# Eurorack_CV_Input.net
KiCad netlist of a schematic drawn in EAGLE
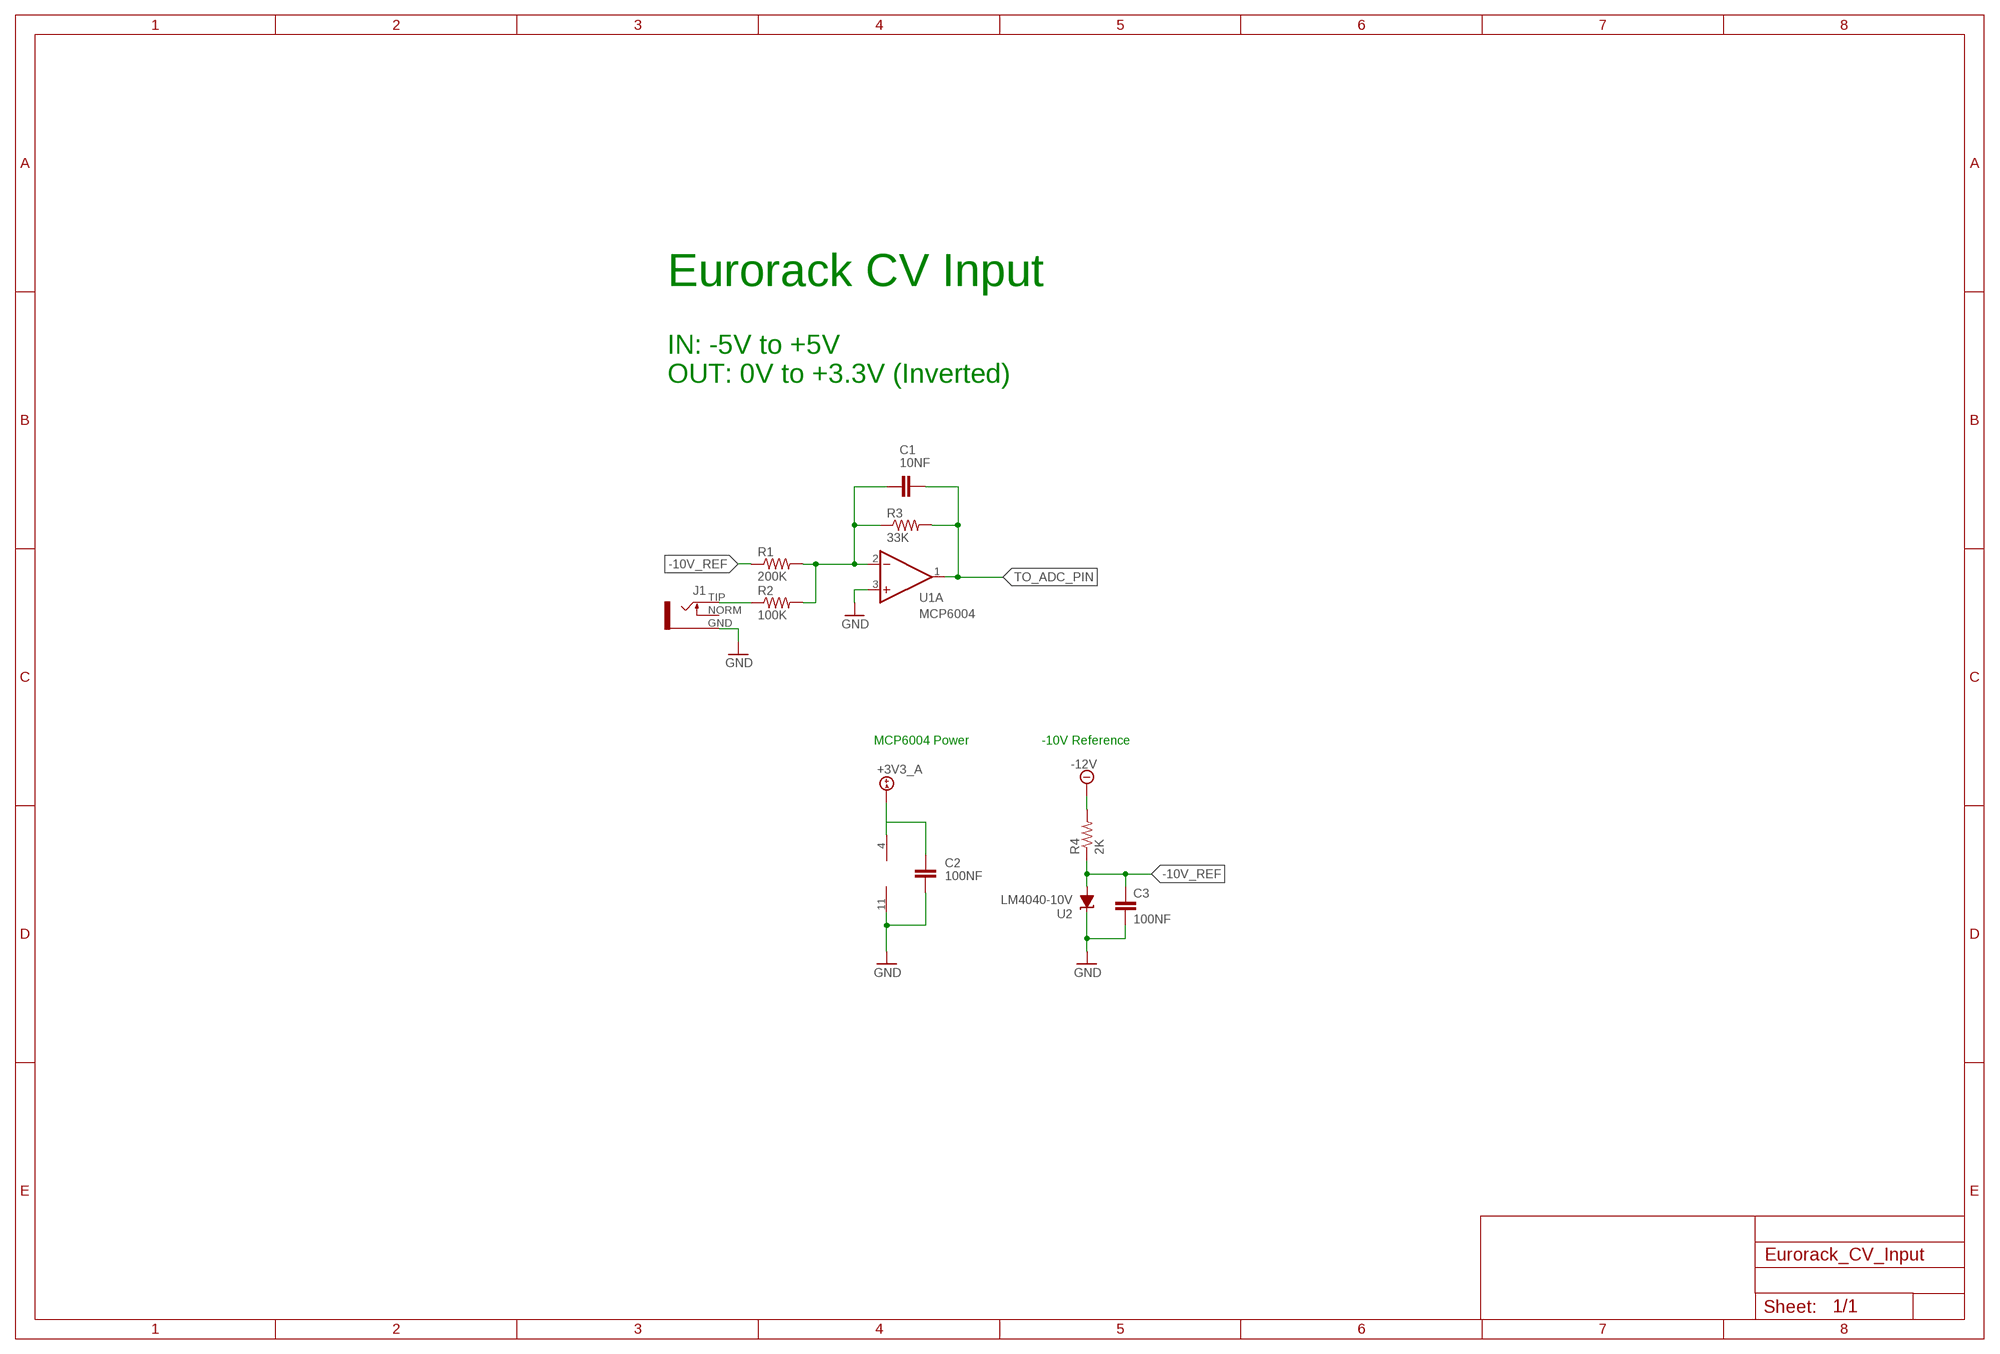
[diagram p0: schematic, sheet 1]

(export (version "E")
  (design (tool "Eeschema 10.0.6"))
  (components
    (comp (ref "C1")
      (value "10NF")
      (footprint "eagle-import:C0603")
      (libsource (lib "eagle-import") (part "C-EUC0603"))
    )
    (comp (ref "C2")
      (value "100NF")
      (footprint "eagle-import:C0603")
      (libsource (lib "eagle-import") (part "C-EUC0603"))
    )
    (comp (ref "C3")
      (value "100NF")
      (footprint "eagle-import:C0603")
      (libsource (lib "eagle-import") (part "C-EUC0603"))
    )
    (comp (ref "J1")
      (value "Eurorack Jack")
      (footprint "eagle-import:S_JACK")
      (libsource (lib "eagle-import") (part "EURO_JACK"))
    )
    (comp (ref "R1")
      (value "200K")
      (footprint "eagle-import:R0603")
      (libsource (lib "eagle-import") (part "R-US_R0603"))
    )
    (comp (ref "R2")
      (value "100K")
      (footprint "eagle-import:R0603")
      (libsource (lib "eagle-import") (part "R-US_R0603"))
    )
    (comp (ref "R3")
      (value "33K")
      (footprint "eagle-import:R0603")
      (libsource (lib "eagle-import") (part "R-US_R0603"))
    )
    (comp (ref "R4")
      (value "2K")
      (footprint "eagle-import:R0603")
      (libsource (lib "eagle-import") (part "R-US_R0603"))
    )
    (comp (ref "U1")
      (value "MCP6004")
      (footprint "eagle-import:TSSOP-14")
      (fields (field (name "MPN") "MCP6004T-E/ST"))
      (libsource (lib "eagle-import") (part "MCP6004_TSSOP-14"))
    )
    (comp (ref "U2")
      (value "LM4040-10V")
      (footprint "eagle-import:DBZ_R-PDSO-G3")
      (fields (field (name "MPN") "LM4041A12IDBZR"))
      (libsource (lib "eagle-import") (part "LM4040-10VDBZA12"))
    )
  )
  (nets
    (net (code "1") (name "+3V3_A") (class "Default")
      (node (ref "C2") (pin "2") (pinfunction "2_2") (pintype "passive"))
      (node (ref "U1") (pin "4") (pinfunction "V+_4") (pintype "power_in"))
    )
    (net (code "2") (name "-10V_REF") (class "Default")
      (node (ref "C3") (pin "1") (pinfunction "1_1") (pintype "passive"))
      (node (ref "R1") (pin "1") (pinfunction "1_1") (pintype "passive"))
      (node (ref "R4") (pin "1") (pinfunction "1_1") (pintype "passive"))
      (node (ref "U2") (pin "2") (pinfunction "A_2") (pintype "passive"))
    )
    (net (code "3") (name "-12V") (class "Default")
      (node (ref "R4") (pin "2") (pinfunction "2_2") (pintype "passive"))
    )
    (net (code "4") (name "GND") (class "Default")
      (node (ref "C2") (pin "1") (pinfunction "1_1") (pintype "passive"))
      (node (ref "C3") (pin "2") (pinfunction "2_2") (pintype "passive"))
      (node (ref "J1") (pin "GND") (pinfunction "GND_GND") (pintype "passive"))
      (node (ref "U1") (pin "11") (pinfunction "V-_11") (pintype "power_in"))
      (node (ref "U1") (pin "3") (pinfunction "+IN_3") (pintype "input"))
      (node (ref "U2") (pin "1") (pinfunction "C_1") (pintype "passive"))
    )
    (net (code "5") (name "Net-(J1-PadTIP)") (class "Default")
      (node (ref "J1") (pin "TIP") (pinfunction "TIP_TIP") (pintype "passive"))
      (node (ref "R2") (pin "1") (pinfunction "1_1") (pintype "passive"))
    )
    (net (code "6") (name "Net-(U1A--IN)") (class "Default")
      (node (ref "C1") (pin "1") (pinfunction "1_1") (pintype "passive"))
      (node (ref "R1") (pin "2") (pinfunction "2_2") (pintype "passive"))
      (node (ref "R2") (pin "2") (pinfunction "2_2") (pintype "passive"))
      (node (ref "R3") (pin "1") (pinfunction "1_1") (pintype "passive"))
      (node (ref "U1") (pin "2") (pinfunction "-IN_2") (pintype "input"))
    )
    (net (code "7") (name "TO_ADC_PIN") (class "Default")
      (node (ref "C1") (pin "2") (pinfunction "2_2") (pintype "passive"))
      (node (ref "R3") (pin "2") (pinfunction "2_2") (pintype "passive"))
      (node (ref "U1") (pin "1") (pinfunction "OUT_1") (pintype "output"))
    )
    (net (code "8") (name "unconnected-(J1-PadNORM)") (class "Default")
      (node (ref "J1") (pin "NORM") (pinfunction "NORM_NORM") (pintype "passive"))
    )
  )
)
